# Analog_1_16.net
KiCad netlist of a schematic drawn in Altium Designer
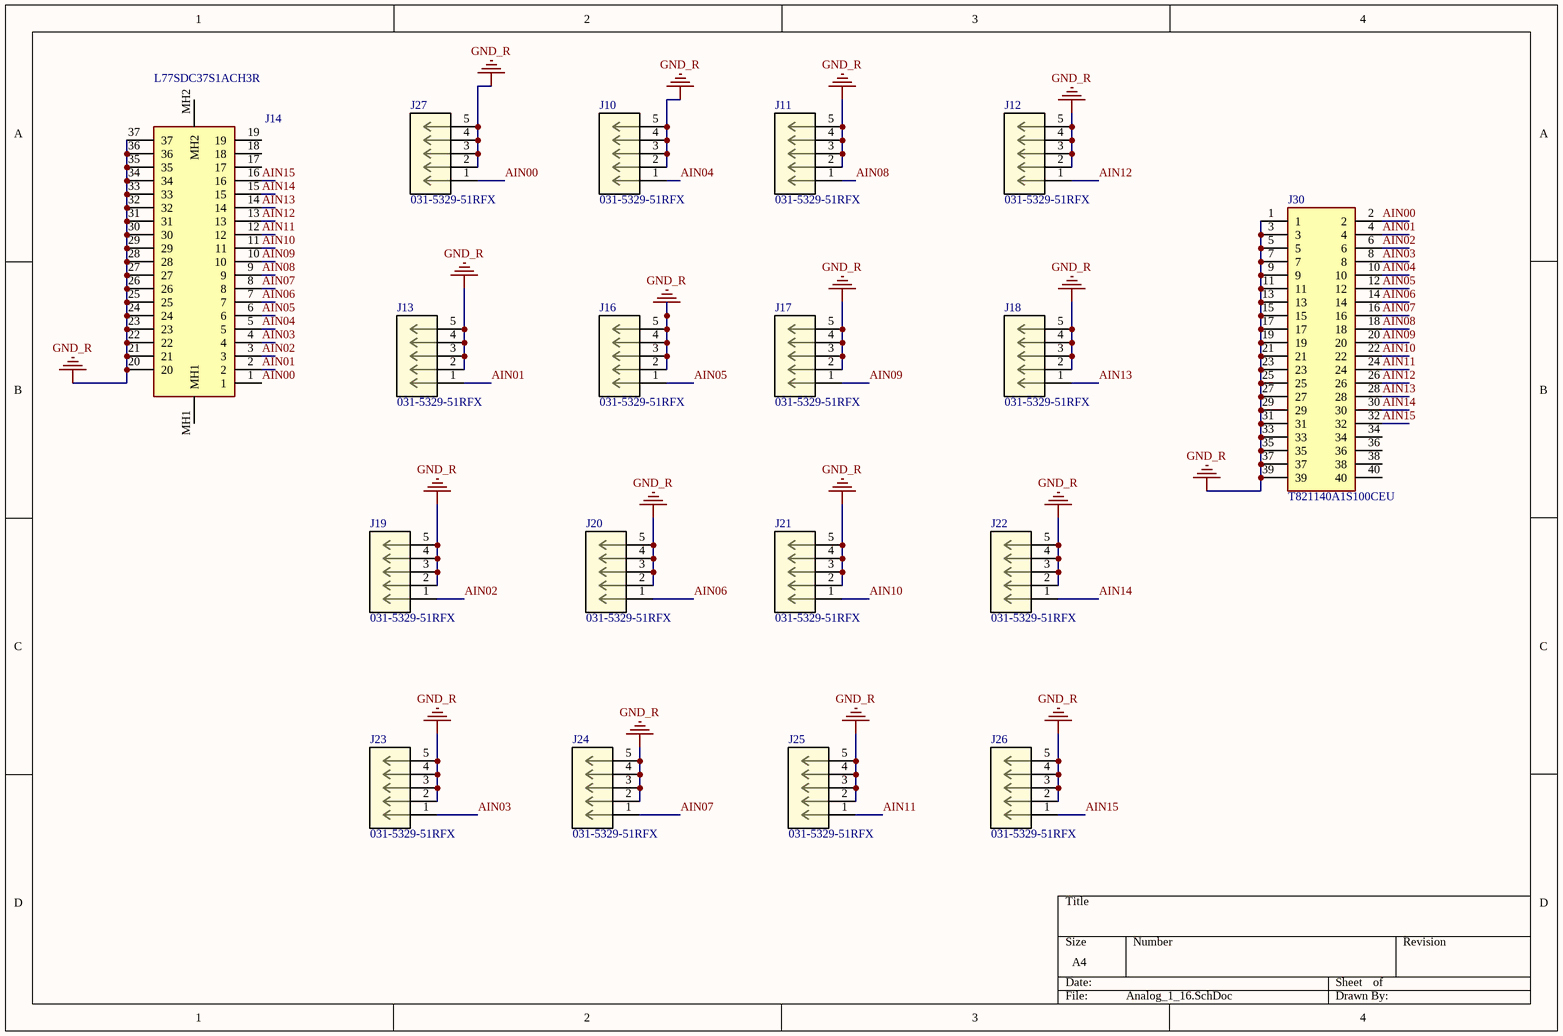
[diagram p0: Analog_1_16.SchDoc]

(export (version "E")
  (design (tool "Eeschema 10.0.6"))
  (components
    (comp (ref "J10")
      (value "031-5329-51RFX")
      (footprint "CONN1_031-5329-51RFX_AMP")
      (description "No Description Available")
      (libsource (lib "Integrated_Library1") (part "031-5329-51RFX"))
    )
    (comp (ref "J11")
      (value "031-5329-51RFX")
      (footprint "CONN1_031-5329-51RFX_AMP")
      (description "No Description Available")
      (libsource (lib "Integrated_Library1") (part "031-5329-51RFX"))
    )
    (comp (ref "J12")
      (value "031-5329-51RFX")
      (footprint "CONN1_031-5329-51RFX_AMP")
      (description "No Description Available")
      (libsource (lib "Integrated_Library1") (part "031-5329-51RFX"))
    )
    (comp (ref "J13")
      (value "031-5329-51RFX")
      (footprint "CONN1_031-5329-51RFX_AMP")
      (description "No Description Available")
      (libsource (lib "Integrated_Library1") (part "031-5329-51RFX"))
    )
    (comp (ref "J14")
      (value "L77SDC37S1ACH3R")
      (footprint "L77SDC37S1ACH3R")
      (description "Connector")
      (fields (field (name "MOUSER PART NUMBER") "523-L77SDC37S1ACH3R"))
      (libsource (lib "opel_Rt_comps") (part "L77SDC37S1ACH3R"))
    )
    (comp (ref "J16")
      (value "031-5329-51RFX")
      (footprint "CONN1_031-5329-51RFX_AMP")
      (description "No Description Available")
      (libsource (lib "Integrated_Library1") (part "031-5329-51RFX"))
    )
    (comp (ref "J17")
      (value "031-5329-51RFX")
      (footprint "CONN1_031-5329-51RFX_AMP")
      (description "No Description Available")
      (libsource (lib "Integrated_Library1") (part "031-5329-51RFX"))
    )
    (comp (ref "J18")
      (value "031-5329-51RFX")
      (footprint "CONN1_031-5329-51RFX_AMP")
      (description "No Description Available")
      (libsource (lib "Integrated_Library1") (part "031-5329-51RFX"))
    )
    (comp (ref "J19")
      (value "031-5329-51RFX")
      (footprint "CONN1_031-5329-51RFX_AMP")
      (description "No Description Available")
      (libsource (lib "Integrated_Library1") (part "031-5329-51RFX"))
    )
    (comp (ref "J20")
      (value "031-5329-51RFX")
      (footprint "CONN1_031-5329-51RFX_AMP")
      (description "No Description Available")
      (libsource (lib "Integrated_Library1") (part "031-5329-51RFX"))
    )
    (comp (ref "J21")
      (value "031-5329-51RFX")
      (footprint "CONN1_031-5329-51RFX_AMP")
      (description "No Description Available")
      (libsource (lib "Integrated_Library1") (part "031-5329-51RFX"))
    )
    (comp (ref "J22")
      (value "031-5329-51RFX")
      (footprint "CONN1_031-5329-51RFX_AMP")
      (description "No Description Available")
      (libsource (lib "Integrated_Library1") (part "031-5329-51RFX"))
    )
    (comp (ref "J23")
      (value "031-5329-51RFX")
      (footprint "CONN1_031-5329-51RFX_AMP")
      (description "No Description Available")
      (libsource (lib "Integrated_Library1") (part "031-5329-51RFX"))
    )
    (comp (ref "J24")
      (value "031-5329-51RFX")
      (footprint "CONN1_031-5329-51RFX_AMP")
      (description "No Description Available")
      (libsource (lib "Integrated_Library1") (part "031-5329-51RFX"))
    )
    (comp (ref "J25")
      (value "031-5329-51RFX")
      (footprint "CONN1_031-5329-51RFX_AMP")
      (description "No Description Available")
      (libsource (lib "Integrated_Library1") (part "031-5329-51RFX"))
    )
    (comp (ref "J26")
      (value "031-5329-51RFX")
      (footprint "CONN1_031-5329-51RFX_AMP")
      (description "No Description Available")
      (libsource (lib "Integrated_Library1") (part "031-5329-51RFX"))
    )
    (comp (ref "J27")
      (value "031-5329-51RFX")
      (footprint "CONN1_031-5329-51RFX_AMP")
      (description "No Description Available")
      (libsource (lib "Integrated_Library1") (part "031-5329-51RFX"))
    )
    (comp (ref "J30")
      (value "T821140A1S100CEU")
      (footprint "SamacSys:SHDR40W64P254X254_2X20_5842X895X915P")
      (description "Connector")
      (libsource (lib "*") (part "T821140A1S100CEU"))
    )
  )
  (nets
    (net (code "1") (name "/AIN00") (class "Default")
      (node (ref "J14") (pin "1") (pinfunction "1_1") (pintype "passive"))
      (node (ref "J27") (pin "1") (pinfunction "1_1") (pintype "passive"))
      (node (ref "J30") (pin "2") (pinfunction "2_2") (pintype "passive"))
    )
    (net (code "2") (name "/AIN01") (class "Default")
      (node (ref "J13") (pin "1") (pinfunction "1_1") (pintype "passive"))
      (node (ref "J14") (pin "2") (pinfunction "2_2") (pintype "passive"))
      (node (ref "J30") (pin "4") (pinfunction "4_4") (pintype "passive"))
    )
    (net (code "3") (name "/AIN02") (class "Default")
      (node (ref "J14") (pin "3") (pinfunction "3_3") (pintype "passive"))
      (node (ref "J19") (pin "1") (pinfunction "1_1") (pintype "passive"))
      (node (ref "J30") (pin "6") (pinfunction "6_6") (pintype "passive"))
    )
    (net (code "4") (name "/AIN03") (class "Default")
      (node (ref "J14") (pin "4") (pinfunction "4_4") (pintype "passive"))
      (node (ref "J23") (pin "1") (pinfunction "1_1") (pintype "passive"))
      (node (ref "J30") (pin "8") (pinfunction "8_8") (pintype "passive"))
    )
    (net (code "5") (name "/AIN04") (class "Default")
      (node (ref "J10") (pin "1") (pinfunction "1_1") (pintype "passive"))
      (node (ref "J14") (pin "5") (pinfunction "5_5") (pintype "passive"))
      (node (ref "J30") (pin "10") (pinfunction "10_10") (pintype "passive"))
    )
    (net (code "6") (name "/AIN05") (class "Default")
      (node (ref "J14") (pin "6") (pinfunction "6_6") (pintype "passive"))
      (node (ref "J16") (pin "1") (pinfunction "1_1") (pintype "passive"))
      (node (ref "J30") (pin "12") (pinfunction "12_12") (pintype "passive"))
    )
    (net (code "7") (name "/AIN06") (class "Default")
      (node (ref "J14") (pin "7") (pinfunction "7_7") (pintype "passive"))
      (node (ref "J20") (pin "1") (pinfunction "1_1") (pintype "passive"))
      (node (ref "J30") (pin "14") (pinfunction "14_14") (pintype "passive"))
    )
    (net (code "8") (name "/AIN07") (class "Default")
      (node (ref "J14") (pin "8") (pinfunction "8_8") (pintype "passive"))
      (node (ref "J24") (pin "1") (pinfunction "1_1") (pintype "passive"))
      (node (ref "J30") (pin "16") (pinfunction "16_16") (pintype "passive"))
    )
    (net (code "9") (name "/AIN08") (class "Default")
      (node (ref "J11") (pin "1") (pinfunction "1_1") (pintype "passive"))
      (node (ref "J14") (pin "9") (pinfunction "9_9") (pintype "passive"))
      (node (ref "J30") (pin "18") (pinfunction "18_18") (pintype "passive"))
    )
    (net (code "10") (name "/AIN09") (class "Default")
      (node (ref "J14") (pin "10") (pinfunction "10_10") (pintype "passive"))
      (node (ref "J17") (pin "1") (pinfunction "1_1") (pintype "passive"))
      (node (ref "J30") (pin "20") (pinfunction "20_20") (pintype "passive"))
    )
    (net (code "11") (name "/AIN10") (class "Default")
      (node (ref "J14") (pin "11") (pinfunction "11_11") (pintype "passive"))
      (node (ref "J21") (pin "1") (pinfunction "1_1") (pintype "passive"))
      (node (ref "J30") (pin "22") (pinfunction "22_22") (pintype "passive"))
    )
    (net (code "12") (name "/AIN11") (class "Default")
      (node (ref "J14") (pin "12") (pinfunction "12_12") (pintype "passive"))
      (node (ref "J25") (pin "1") (pinfunction "1_1") (pintype "passive"))
      (node (ref "J30") (pin "24") (pinfunction "24_24") (pintype "passive"))
    )
    (net (code "13") (name "/AIN12") (class "Default")
      (node (ref "J12") (pin "1") (pinfunction "1_1") (pintype "passive"))
      (node (ref "J14") (pin "13") (pinfunction "13_13") (pintype "passive"))
      (node (ref "J30") (pin "26") (pinfunction "26_26") (pintype "passive"))
    )
    (net (code "14") (name "/AIN13") (class "Default")
      (node (ref "J14") (pin "14") (pinfunction "14_14") (pintype "passive"))
      (node (ref "J18") (pin "1") (pinfunction "1_1") (pintype "passive"))
      (node (ref "J30") (pin "28") (pinfunction "28_28") (pintype "passive"))
    )
    (net (code "15") (name "/AIN14") (class "Default")
      (node (ref "J14") (pin "15") (pinfunction "15_15") (pintype "passive"))
      (node (ref "J22") (pin "1") (pinfunction "1_1") (pintype "passive"))
      (node (ref "J30") (pin "30") (pinfunction "30_30") (pintype "passive"))
    )
    (net (code "16") (name "/AIN15") (class "Default")
      (node (ref "J14") (pin "16") (pinfunction "16_16") (pintype "passive"))
      (node (ref "J26") (pin "1") (pinfunction "1_1") (pintype "passive"))
      (node (ref "J30") (pin "32") (pinfunction "32_32") (pintype "passive"))
    )
    (net (code "17") (name "GND_R") (class "Default")
      (node (ref "J10") (pin "2") (pinfunction "2_2") (pintype "passive"))
      (node (ref "J10") (pin "3") (pinfunction "3_3") (pintype "passive"))
      (node (ref "J10") (pin "4") (pinfunction "4_4") (pintype "passive"))
      (node (ref "J10") (pin "5") (pinfunction "5_5") (pintype "passive"))
      (node (ref "J11") (pin "2") (pinfunction "2_2") (pintype "passive"))
      (node (ref "J11") (pin "3") (pinfunction "3_3") (pintype "passive"))
      (node (ref "J11") (pin "4") (pinfunction "4_4") (pintype "passive"))
      (node (ref "J11") (pin "5") (pinfunction "5_5") (pintype "passive"))
      (node (ref "J12") (pin "2") (pinfunction "2_2") (pintype "passive"))
      (node (ref "J12") (pin "3") (pinfunction "3_3") (pintype "passive"))
      (node (ref "J12") (pin "4") (pinfunction "4_4") (pintype "passive"))
      (node (ref "J12") (pin "5") (pinfunction "5_5") (pintype "passive"))
      (node (ref "J13") (pin "2") (pinfunction "2_2") (pintype "passive"))
      (node (ref "J13") (pin "3") (pinfunction "3_3") (pintype "passive"))
      (node (ref "J13") (pin "4") (pinfunction "4_4") (pintype "passive"))
      (node (ref "J13") (pin "5") (pinfunction "5_5") (pintype "passive"))
      (node (ref "J14") (pin "20") (pinfunction "20_20") (pintype "passive"))
      (node (ref "J14") (pin "21") (pinfunction "21_21") (pintype "passive"))
      (node (ref "J14") (pin "22") (pinfunction "22_22") (pintype "passive"))
      (node (ref "J14") (pin "23") (pinfunction "23_23") (pintype "passive"))
      (node (ref "J14") (pin "24") (pinfunction "24_24") (pintype "passive"))
      (node (ref "J14") (pin "25") (pinfunction "25_25") (pintype "passive"))
      (node (ref "J14") (pin "26") (pinfunction "26_26") (pintype "passive"))
      (node (ref "J14") (pin "27") (pinfunction "27_27") (pintype "passive"))
      (node (ref "J14") (pin "28") (pinfunction "28_28") (pintype "passive"))
      (node (ref "J14") (pin "29") (pinfunction "29_29") (pintype "passive"))
      (node (ref "J14") (pin "30") (pinfunction "30_30") (pintype "passive"))
      (node (ref "J14") (pin "31") (pinfunction "31_31") (pintype "passive"))
      (node (ref "J14") (pin "32") (pinfunction "32_32") (pintype "passive"))
      (node (ref "J14") (pin "33") (pinfunction "33_33") (pintype "passive"))
      (node (ref "J14") (pin "34") (pinfunction "34_34") (pintype "passive"))
      (node (ref "J14") (pin "35") (pinfunction "35_35") (pintype "passive"))
      (node (ref "J14") (pin "36") (pinfunction "36_36") (pintype "passive"))
      (node (ref "J14") (pin "37") (pinfunction "37_37") (pintype "passive"))
      (node (ref "J16") (pin "2") (pinfunction "2_2") (pintype "passive"))
      (node (ref "J16") (pin "3") (pinfunction "3_3") (pintype "passive"))
      (node (ref "J16") (pin "4") (pinfunction "4_4") (pintype "passive"))
      (node (ref "J16") (pin "5") (pinfunction "5_5") (pintype "passive"))
      (node (ref "J17") (pin "2") (pinfunction "2_2") (pintype "passive"))
      (node (ref "J17") (pin "3") (pinfunction "3_3") (pintype "passive"))
      (node (ref "J17") (pin "4") (pinfunction "4_4") (pintype "passive"))
      (node (ref "J17") (pin "5") (pinfunction "5_5") (pintype "passive"))
      (node (ref "J18") (pin "2") (pinfunction "2_2") (pintype "passive"))
      (node (ref "J18") (pin "3") (pinfunction "3_3") (pintype "passive"))
      (node (ref "J18") (pin "4") (pinfunction "4_4") (pintype "passive"))
      (node (ref "J18") (pin "5") (pinfunction "5_5") (pintype "passive"))
      (node (ref "J19") (pin "2") (pinfunction "2_2") (pintype "passive"))
      (node (ref "J19") (pin "3") (pinfunction "3_3") (pintype "passive"))
      (node (ref "J19") (pin "4") (pinfunction "4_4") (pintype "passive"))
      (node (ref "J19") (pin "5") (pinfunction "5_5") (pintype "passive"))
      (node (ref "J20") (pin "2") (pinfunction "2_2") (pintype "passive"))
      (node (ref "J20") (pin "3") (pinfunction "3_3") (pintype "passive"))
      (node (ref "J20") (pin "4") (pinfunction "4_4") (pintype "passive"))
      (node (ref "J20") (pin "5") (pinfunction "5_5") (pintype "passive"))
      (node (ref "J21") (pin "2") (pinfunction "2_2") (pintype "passive"))
      (node (ref "J21") (pin "3") (pinfunction "3_3") (pintype "passive"))
      (node (ref "J21") (pin "4") (pinfunction "4_4") (pintype "passive"))
      (node (ref "J21") (pin "5") (pinfunction "5_5") (pintype "passive"))
      (node (ref "J22") (pin "2") (pinfunction "2_2") (pintype "passive"))
      (node (ref "J22") (pin "3") (pinfunction "3_3") (pintype "passive"))
      (node (ref "J22") (pin "4") (pinfunction "4_4") (pintype "passive"))
      (node (ref "J22") (pin "5") (pinfunction "5_5") (pintype "passive"))
      (node (ref "J23") (pin "2") (pinfunction "2_2") (pintype "passive"))
      (node (ref "J23") (pin "3") (pinfunction "3_3") (pintype "passive"))
      (node (ref "J23") (pin "4") (pinfunction "4_4") (pintype "passive"))
      (node (ref "J23") (pin "5") (pinfunction "5_5") (pintype "passive"))
      (node (ref "J24") (pin "2") (pinfunction "2_2") (pintype "passive"))
      (node (ref "J24") (pin "3") (pinfunction "3_3") (pintype "passive"))
      (node (ref "J24") (pin "4") (pinfunction "4_4") (pintype "passive"))
      (node (ref "J24") (pin "5") (pinfunction "5_5") (pintype "passive"))
      (node (ref "J25") (pin "2") (pinfunction "2_2") (pintype "passive"))
      (node (ref "J25") (pin "3") (pinfunction "3_3") (pintype "passive"))
      (node (ref "J25") (pin "4") (pinfunction "4_4") (pintype "passive"))
      (node (ref "J25") (pin "5") (pinfunction "5_5") (pintype "passive"))
      (node (ref "J26") (pin "2") (pinfunction "2_2") (pintype "passive"))
      (node (ref "J26") (pin "3") (pinfunction "3_3") (pintype "passive"))
      (node (ref "J26") (pin "4") (pinfunction "4_4") (pintype "passive"))
      (node (ref "J26") (pin "5") (pinfunction "5_5") (pintype "passive"))
      (node (ref "J27") (pin "2") (pinfunction "2_2") (pintype "passive"))
      (node (ref "J27") (pin "3") (pinfunction "3_3") (pintype "passive"))
      (node (ref "J27") (pin "4") (pinfunction "4_4") (pintype "passive"))
      (node (ref "J27") (pin "5") (pinfunction "5_5") (pintype "passive"))
      (node (ref "J30") (pin "1") (pinfunction "1_1") (pintype "passive"))
      (node (ref "J30") (pin "11") (pinfunction "11_11") (pintype "passive"))
      (node (ref "J30") (pin "13") (pinfunction "13_13") (pintype "passive"))
      (node (ref "J30") (pin "15") (pinfunction "15_15") (pintype "passive"))
      (node (ref "J30") (pin "17") (pinfunction "17_17") (pintype "passive"))
      (node (ref "J30") (pin "19") (pinfunction "19_19") (pintype "passive"))
      (node (ref "J30") (pin "21") (pinfunction "21_21") (pintype "passive"))
      (node (ref "J30") (pin "23") (pinfunction "23_23") (pintype "passive"))
      (node (ref "J30") (pin "25") (pinfunction "25_25") (pintype "passive"))
      (node (ref "J30") (pin "27") (pinfunction "27_27") (pintype "passive"))
      (node (ref "J30") (pin "29") (pinfunction "29_29") (pintype "passive"))
      (node (ref "J30") (pin "3") (pinfunction "3_3") (pintype "passive"))
      (node (ref "J30") (pin "31") (pinfunction "31_31") (pintype "passive"))
      (node (ref "J30") (pin "33") (pinfunction "33_33") (pintype "passive"))
      (node (ref "J30") (pin "35") (pinfunction "35_35") (pintype "passive"))
      (node (ref "J30") (pin "37") (pinfunction "37_37") (pintype "passive"))
      (node (ref "J30") (pin "39") (pinfunction "39_39") (pintype "passive"))
      (node (ref "J30") (pin "5") (pinfunction "5_5") (pintype "passive"))
      (node (ref "J30") (pin "7") (pinfunction "7_7") (pintype "passive"))
      (node (ref "J30") (pin "9") (pinfunction "9_9") (pintype "passive"))
    )
    (net (code "18") (name "unconnected-(J14-Pad17)") (class "Default")
      (node (ref "J14") (pin "17") (pinfunction "17_17") (pintype "passive"))
    )
    (net (code "19") (name "unconnected-(J14-Pad18)") (class "Default")
      (node (ref "J14") (pin "18") (pinfunction "18_18") (pintype "passive"))
    )
    (net (code "20") (name "unconnected-(J14-Pad19)") (class "Default")
      (node (ref "J14") (pin "19") (pinfunction "19_19") (pintype "passive"))
    )
    (net (code "21") (name "unconnected-(J14-PadMH1)") (class "Default")
      (node (ref "J14") (pin "MH1") (pinfunction "MH1_MH1") (pintype "passive"))
    )
    (net (code "22") (name "unconnected-(J14-PadMH2)") (class "Default")
      (node (ref "J14") (pin "MH2") (pinfunction "MH2_MH2") (pintype "passive"))
    )
    (net (code "23") (name "unconnected-(J30-Pad34)") (class "Default")
      (node (ref "J30") (pin "34") (pinfunction "34_34") (pintype "passive"))
    )
    (net (code "24") (name "unconnected-(J30-Pad36)") (class "Default")
      (node (ref "J30") (pin "36") (pinfunction "36_36") (pintype "passive"))
    )
    (net (code "25") (name "unconnected-(J30-Pad38)") (class "Default")
      (node (ref "J30") (pin "38") (pinfunction "38_38") (pintype "passive"))
    )
    (net (code "26") (name "unconnected-(J30-Pad40)") (class "Default")
      (node (ref "J30") (pin "40") (pinfunction "40_40") (pintype "passive"))
    )
  )
)
